# attinier84-motherboard-pth-mk-1_0.net
KiCad netlist of a schematic drawn in EAGLE
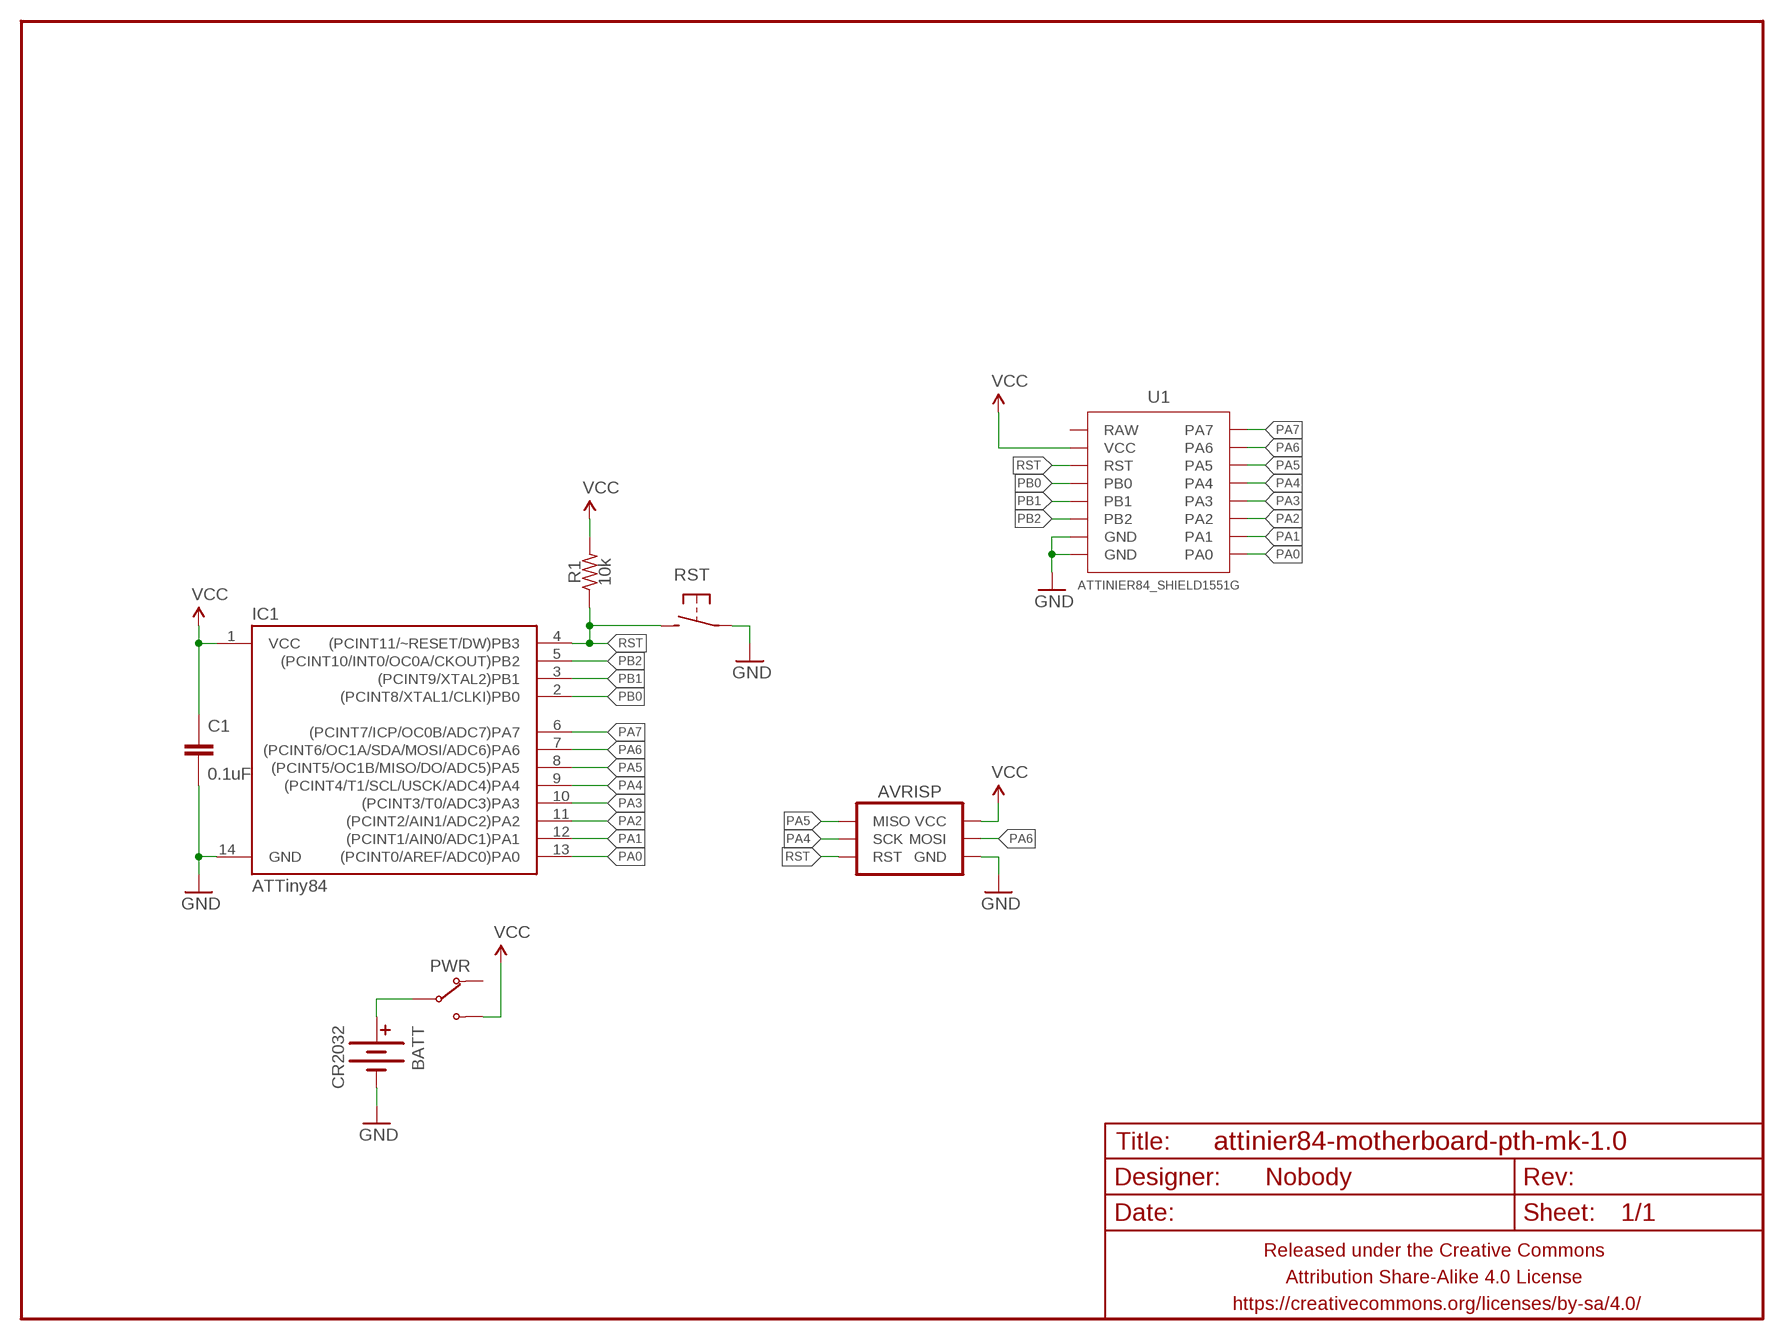
[diagram p0: schematic, sheet 1]

(export (version "E")
  (design (tool "Eeschema 10.0.6"))
  (components
    (comp (ref "AVRISP")
      (value "AVR_SPI_PRG_6PTH")
      (footprint "eagle-import:2X3")
      (libsource (lib "eagle-import") (part "AVR_SPI_PRG_6PTH"))
    )
    (comp (ref "BATT")
      (value "CR2032")
      (footprint "eagle-import:BATTCON_20MM_PTH_TOPLOAD")
      (libsource (lib "eagle-import") (part "BATTERY20PTH_TOPLOAD"))
    )
    (comp (ref "C1")
      (value "0.1uF")
      (footprint "eagle-import:C025-024X044")
      (libsource (lib "eagle-import") (part "CAPACITOR-CERAMIC025-024X044"))
    )
    (comp (ref "FRAME1")
      (value "FRAME-LETTERNO_PACKAGE")
      (footprint "eagle-import:DUMMY")
      (fields (field (name "DESIGNER") "Nobody"))
      (libsource (lib "eagle-import") (part "FRAME-LETTERNO_PACKAGE"))
    )
    (comp (ref "IC1")
      (value "ATTiny84")
      (footprint "eagle-import:DIL14")
      (libsource (lib "eagle-import") (part "ATTINY84ATTINY84-20PU"))
    )
    (comp (ref "PWR")
      (value "SWITCH-SPDTPTH-RA-2.54MM")
      (footprint "eagle-import:SPDT-RA-2.54MM")
      (libsource (lib "eagle-import") (part "SWITCH-SPDTPTH-RA-2.54MM"))
    )
    (comp (ref "R1")
      (value "10k")
      (footprint "eagle-import:RESISTOR-AXIAL-PTH-7.62MM")
      (libsource (lib "eagle-import") (part "RESISTORPTH-AXIAL-7.62MM"))
    )
    (comp (ref "RST")
      (value "SPST-NO-TACT3MM-RA")
      (footprint "eagle-import:TACTILE-PTH-SIDE")
      (libsource (lib "eagle-import") (part "SPST-NO-TACT3MM-RA"))
    )
    (comp (ref "U1")
      (value "ATTINIER84_SHIELD1551G")
      (footprint "eagle-import:ATTINIER84_SHIELD2")
      (libsource (lib "eagle-import") (part "ATTINIER84_SHIELD1551G"))
    )
  )
  (nets
    (net (code "1") (name "GND") (class "Default")
      (node (ref "AVRISP") (pin "6") (pinfunction "GND_6") (pintype "passive"))
      (node (ref "BATT") (pin "-") (pinfunction "-_-") (pintype "power_in"))
      (node (ref "C1") (pin "2") (pinfunction "2_2") (pintype "passive"))
      (node (ref "IC1") (pin "14") (pinfunction "GND_14") (pintype "bidirectional"))
      (node (ref "RST") (pin "1") (pinfunction "1_1") (pintype "passive"))
      (node (ref "U1") (pin "GND@1") (pinfunction "GND_GND@1") (pintype "bidirectional"))
      (node (ref "U1") (pin "GND@2") (pinfunction "GND_GND@2") (pintype "bidirectional"))
    )
    (net (code "2") (name "Net-(PWR-COM)") (class "Default")
      (node (ref "BATT") (pin "+") (pinfunction "+_+") (pintype "power_in"))
      (node (ref "PWR") (pin "2") (pinfunction "COM_2") (pintype "passive"))
    )
    (net (code "3") (name "PA0") (class "Default")
      (node (ref "IC1") (pin "13") (pinfunction "(PCINT0/AREF/ADC0)PA0_13") (pintype "bidirectional"))
      (node (ref "U1") (pin "PA0") (pinfunction "PA0_PA0") (pintype "bidirectional"))
    )
    (net (code "4") (name "PA1") (class "Default")
      (node (ref "IC1") (pin "12") (pinfunction "(PCINT1/AIN0/ADC1)PA1_12") (pintype "bidirectional"))
      (node (ref "U1") (pin "PA1") (pinfunction "PA1_PA1") (pintype "bidirectional"))
    )
    (net (code "5") (name "PA2") (class "Default")
      (node (ref "IC1") (pin "11") (pinfunction "(PCINT2/AIN1/ADC2)PA2_11") (pintype "bidirectional"))
      (node (ref "U1") (pin "PA2") (pinfunction "PA2_PA2") (pintype "bidirectional"))
    )
    (net (code "6") (name "PA3") (class "Default")
      (node (ref "IC1") (pin "10") (pinfunction "(PCINT3/T0/ADC3)PA3_10") (pintype "bidirectional"))
      (node (ref "U1") (pin "PA3") (pinfunction "PA3_PA3") (pintype "bidirectional"))
    )
    (net (code "7") (name "PA4") (class "Default")
      (node (ref "AVRISP") (pin "3") (pinfunction "SCK_3") (pintype "passive"))
      (node (ref "IC1") (pin "9") (pinfunction "(PCINT4/T1/SCL/USCK/ADC4)PA4_9") (pintype "bidirectional"))
      (node (ref "U1") (pin "PA4") (pinfunction "PA4_PA4") (pintype "bidirectional"))
    )
    (net (code "8") (name "PA5") (class "Default")
      (node (ref "AVRISP") (pin "1") (pinfunction "MISO_1") (pintype "passive"))
      (node (ref "IC1") (pin "8") (pinfunction "(PCINT5/OC1B/MISO/DO/ADC5)PA5_8") (pintype "bidirectional"))
      (node (ref "U1") (pin "PA5") (pinfunction "PA5_PA5") (pintype "bidirectional"))
    )
    (net (code "9") (name "PA6") (class "Default")
      (node (ref "AVRISP") (pin "4") (pinfunction "MOSI_4") (pintype "passive"))
      (node (ref "IC1") (pin "7") (pinfunction "(PCINT6/OC1A/SDA/MOSI/ADC6)PA6_7") (pintype "bidirectional"))
      (node (ref "U1") (pin "PA6") (pinfunction "PA6_PA6") (pintype "bidirectional"))
    )
    (net (code "10") (name "PA7") (class "Default")
      (node (ref "IC1") (pin "6") (pinfunction "(PCINT7/ICP/OC0B/ADC7)PA7_6") (pintype "bidirectional"))
      (node (ref "U1") (pin "PA7") (pinfunction "PA7_PA7") (pintype "bidirectional"))
    )
    (net (code "11") (name "PB0") (class "Default")
      (node (ref "IC1") (pin "2") (pinfunction "(PCINT8/XTAL1/CLKI)PB0_2") (pintype "bidirectional"))
      (node (ref "U1") (pin "PB0") (pinfunction "PB0_PB0") (pintype "bidirectional"))
    )
    (net (code "12") (name "PB1") (class "Default")
      (node (ref "IC1") (pin "3") (pinfunction "(PCINT9/XTAL2)PB1_3") (pintype "bidirectional"))
      (node (ref "U1") (pin "PB1") (pinfunction "PB1_PB1") (pintype "bidirectional"))
    )
    (net (code "13") (name "PB2") (class "Default")
      (node (ref "IC1") (pin "5") (pinfunction "(PCINT10/INT0/OC0A/CKOUT)PB2_5") (pintype "bidirectional"))
      (node (ref "U1") (pin "PB2") (pinfunction "PB2_PB2") (pintype "bidirectional"))
    )
    (net (code "14") (name "RST") (class "Default")
      (node (ref "AVRISP") (pin "5") (pinfunction "RST_5") (pintype "passive"))
      (node (ref "IC1") (pin "4") (pinfunction "(PCINT11/~{RESET/DW})PB3_4") (pintype "bidirectional"))
      (node (ref "R1") (pin "P$1") (pinfunction "1_P$1") (pintype "passive"))
      (node (ref "RST") (pin "2") (pinfunction "2_2") (pintype "passive"))
      (node (ref "U1") (pin "RST") (pinfunction "RST_RST") (pintype "bidirectional"))
    )
    (net (code "15") (name "VCC") (class "Default")
      (node (ref "AVRISP") (pin "2") (pinfunction "VCC_2") (pintype "passive"))
      (node (ref "C1") (pin "1") (pinfunction "1_1") (pintype "passive"))
      (node (ref "IC1") (pin "1") (pinfunction "VCC_1") (pintype "bidirectional"))
      (node (ref "PWR") (pin "3") (pinfunction "NO_3") (pintype "passive"))
      (node (ref "R1") (pin "P$2") (pinfunction "2_P$2") (pintype "passive"))
      (node (ref "U1") (pin "VCC") (pinfunction "VCC_VCC") (pintype "bidirectional"))
    )
    (net (code "16") (name "unconnected-(PWR-NC-Pad1)") (class "Default")
      (node (ref "PWR") (pin "1") (pinfunction "NC_1") (pintype "passive"))
    )
    (net (code "17") (name "unconnected-(U1-PadRAW)") (class "Default")
      (node (ref "U1") (pin "RAW") (pinfunction "RAW_RAW") (pintype "bidirectional"))
    )
  )
)
